# Power_Supply_HV.net
KiCad netlist of a schematic drawn in Altium Designer
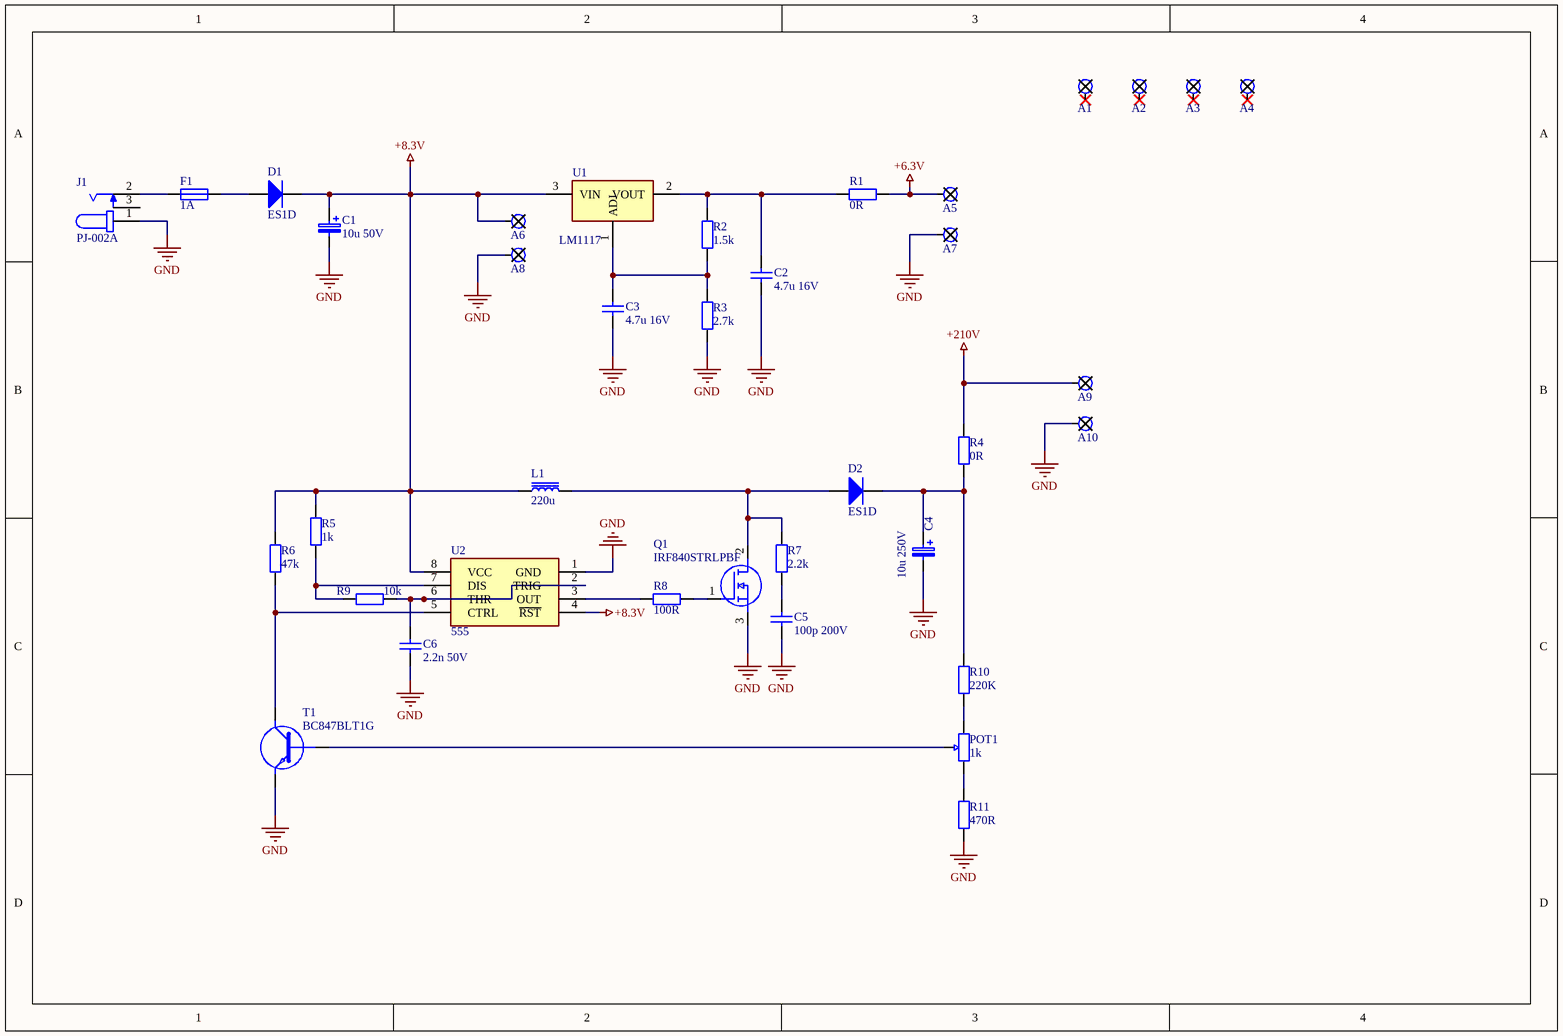
[diagram p0: Power_Supply_HV.SchDoc]

(export (version "E")
  (design (tool "Eeschema 10.0.6"))
  (components
    (comp (ref "A1")
      (value "6mm")
      (footprint "FOOTPRINTS:HOLE M6")
      (description "Mechanical M6 Hole")
      (libsource (lib "SYMBOLS") (part "Mechanical M6 Hole"))
    )
    (comp (ref "A2")
      (value "6mm")
      (footprint "FOOTPRINTS:HOLE M6")
      (description "Mechanical M6 Hole")
      (libsource (lib "SYMBOLS") (part "Mechanical M6 Hole"))
    )
    (comp (ref "A3")
      (value "6mm")
      (footprint "FOOTPRINTS:HOLE M6")
      (description "Mechanical M6 Hole")
      (libsource (lib "SYMBOLS") (part "Mechanical M6 Hole"))
    )
    (comp (ref "A4")
      (value "6mm")
      (footprint "FOOTPRINTS:HOLE M6")
      (description "Mechanical M6 Hole")
      (libsource (lib "SYMBOLS") (part "Mechanical M6 Hole"))
    )
    (comp (ref "A5")
      (value "3mm")
      (footprint "FOOTPRINTS:HOLE M3")
      (description "Mechanical M3 Hole")
      (libsource (lib "SYMBOLS") (part "Mechanical M3 Hole"))
    )
    (comp (ref "A6")
      (value "3mm")
      (footprint "FOOTPRINTS:HOLE M3")
      (description "Mechanical M3 Hole")
      (libsource (lib "SYMBOLS") (part "Mechanical M3 Hole"))
    )
    (comp (ref "A7")
      (value "3mm")
      (footprint "FOOTPRINTS:HOLE M3")
      (description "Mechanical M3 Hole")
      (libsource (lib "SYMBOLS") (part "Mechanical M3 Hole"))
    )
    (comp (ref "A8")
      (value "3mm")
      (footprint "FOOTPRINTS:HOLE M3")
      (description "Mechanical M3 Hole")
      (libsource (lib "SYMBOLS") (part "Mechanical M3 Hole"))
    )
    (comp (ref "A9")
      (value "3mm")
      (footprint "FOOTPRINTS:HOLE M3")
      (description "Mechanical M3 Hole")
      (libsource (lib "SYMBOLS") (part "Mechanical M3 Hole"))
    )
    (comp (ref "A10")
      (value "3mm")
      (footprint "FOOTPRINTS:HOLE M3")
      (description "Mechanical M3 Hole")
      (libsource (lib "SYMBOLS") (part "Mechanical M3 Hole"))
    )
    (comp (ref "C1")
      (value "10u 50V")
      (footprint "FOOTPRINTS:CAPACITOR 6.3X11MM THT")
      (description "Aluminum Electrolytic Capacitors - Radial Leaded WCAP-ATET 10uF 50V 20% Radial")
      (fields
        (field (name "MANUFACTURER") "Wurth Elektronik")
        (field (name "MANUFACTURER PART NUMBER") "860130673001")
      )
      (libsource (lib "SYMBOLS") (part "Capacitor 10u 50V 20% Aluminum 6.3x11mm THT"))
    )
    (comp (ref "C2")
      (value "4.7u 16V")
      (footprint "FOOTPRINTS:CAPACITOR 0805")
      (description "Multilayer Ceramic Capacitors MLCC - SMD/SMT 0805 16VDC 4.7uF 10% X7R")
      (fields
        (field (name "MANUFACTURER") "Taiyo Yuden")
        (field (name "MANUFACTURER PART NUMBER") "EMK212B7475KG-T")
      )
      (libsource (lib "SYMBOLS") (part "Capacitor 4.7u 16V 10% X7R 0805"))
    )
    (comp (ref "C3")
      (value "4.7u 16V")
      (footprint "FOOTPRINTS:CAPACITOR 0805")
      (description "Multilayer Ceramic Capacitors MLCC - SMD/SMT 0805 16VDC 4.7uF 10% X7R")
      (fields
        (field (name "MANUFACTURER") "Taiyo Yuden")
        (field (name "MANUFACTURER PART NUMBER") "EMK212B7475KG-T")
      )
      (libsource (lib "SYMBOLS") (part "Capacitor 4.7u 16V 10% X7R 0805"))
    )
    (comp (ref "C4")
      (value "10u 250V")
      (footprint "FOOTPRINTS:CAPACITOR 10X20MM THT")
      (description "Aluminum Electrolytic Capacitors - Radial Leaded 25V 100uF 105C 6.3x11mm")
      (fields
        (field (name "MANUFACTURER") "Producent")
        (field (name "MANUFACTURER PART NUMBER") "PJ2E100MNN1020")
      )
      (libsource (lib "SYMBOLS") (part "Capacitor 10u 250V 20% Aluminum 10x20mm THT"))
    )
    (comp (ref "C5")
      (value "100p 200V")
      (footprint "FOOTPRINTS:CAPACITOR 1206")
      (description "Multilayer Ceramic Capacitors MLCC - SMD/SMT 200V 100pF X7R 1206 10% AEC-Q200")
      (fields
        (field (name "MANUFACTURER") "KEMET")
        (field (name "MANUFACTURER PART NUMBER") "C1206C101K2RACAUTO")
      )
      (libsource (lib "SYMBOLS") (part "Capacitor 100p 200V 10% X7R 1206"))
    )
    (comp (ref "C6")
      (value "2.2n 50V")
      (footprint "FOOTPRINTS:CAPACITOR 0603")
      (description "Multilayer Ceramic Capacitors MLCC - SMD/SMT 0603 50VDC 2200pF 10% X7R AEC-Q200")
      (fields
        (field (name "MANUFACTURER") "Taiyo Yuden")
        (field (name "MANUFACTURER PART NUMBER") "UMK107B7222KAHT")
      )
      (libsource (lib "SYMBOLS") (part "Capacitor 2.2n 50V 10% X7R 0603"))
    )
    (comp (ref "D1")
      (value "ES1D")
      (footprint "FOOTPRINTS:DIODE DO-214AC")
      (description "Rectifiers 1.0a Rectifier UF Recovery")
      (fields (field (name "MANUFACTURER") "onsemi / Fairchild"))
      (libsource (lib "SYMBOLS") (part "Diode 200V 1.5W 1A Rectifier Vf 920mV ES1D"))
    )
    (comp (ref "D2")
      (value "ES1D")
      (footprint "FOOTPRINTS:DIODE DO-214AC")
      (description "Rectifiers 1.0a Rectifier UF Recovery")
      (fields (field (name "MANUFACTURER") "onsemi / Fairchild"))
      (libsource (lib "SYMBOLS") (part "Diode 200V 1.5W 1A Rectifier Vf 920mV ES1D"))
    )
    (comp (ref "F1")
      (value "1A")
      (footprint "FOOTPRINTS:FUSE 1206")
      (description "Surface Mount Fuses 1A 63V TIME DELAY")
      (fields
        (field (name "MANUFACTURER") "Bourns")
        (field (name "MANUFACTURER PART NUMBER") "SF-1206HI100M-2")
      )
      (libsource (lib "SYMBOLS") (part "Fuse 1A 1% 1/4W 1206"))
    )
    (comp (ref "J1")
      (value "PJ-002A")
      (footprint "FOOTPRINTS:Mechanical CUI_PJ-002A")
      (description "DC Power Connectors Power Jacks")
      (fields (field (name "MANUFACTURER") "https://pl.mouser.com/datasheet/2/670/pj_002a-1778764.pdf"))
      (libsource (lib "SYMBOLS") (part "Mechanical DC Power Connectors Power Jacks"))
    )
    (comp (ref "L1")
      (value "220u")
      (footprint "FOOTPRINTS:INDUCTOR CDRH127")
      (description "Power Inductors - SMD 220uH 0.95A Dual wind inductor")
      (fields
        (field (name "MANUFACTURER") "Murata Power Solutions")
        (field (name "MANUFACTURER PART NUMBER") "49221C")
      )
      (libsource (lib "SYMBOLS") (part "Inductor 220uH 0.95A Shielded 49221C"))
    )
    (comp (ref "POT1")
      (value "1k")
      (footprint "FOOTPRINTS:POTENTIOMETER TC33X")
      (description "Trimmer Resistors - SMD TRIMMER-3MM OPEN FRAME")
      (fields (field (name "MANUFACTURER") "Bourns") (field (name "MANUFACTURER PART NUMBER") "TC33X-1-102E"))
      (libsource (lib "SYMBOLS") (part "Potentiometer PCB 1k SMD TC33X-1-102E"))
    )
    (comp (ref "Q1")
      (value "IRF840STRLPBF")
      (footprint "FOOTPRINTS:TO-263-3")
      (description "MOSFET 500V N-CH HEXFET D2-PA")
      (fields (field (name "MANUFACTURER") "Vishay Semiconductors"))
      (libsource (lib "SYMBOLS") (part "Transistor N-MOSFET 500V 8A TO-263-3 IRF840STRLPBF"))
    )
    (comp (ref "R1")
      (value "0R")
      (footprint "FOOTPRINTS:RESISTOR 0603")
      (description "Thick Film Resistors - SMD 0 Ohms 100 mW 0603 5%")
      (fields
        (field (name "MANUFACTURER") "Yageo")
        (field (name "MANUFACTURER PART NUMBER") "RC0603JR-070RL")
      )
      (libsource (lib "") (part "Resistor 0R 1% 1/10W 0603_1"))
    )
    (comp (ref "R2")
      (value "1.5k")
      (footprint "FOOTPRINTS:RESISTOR 0603")
      (description "Thin Film Resistors - SMD 1/10W 1.5K ohm 1% 50ppm")
      (fields
        (field (name "MANUFACTURER") "Yageo")
        (field (name "MANUFACTURER PART NUMBER") "RT0603FRE071K5L")
      )
      (libsource (lib "SYMBOLS") (part "Resistor 1.5k 1% 1/10W 0603"))
    )
    (comp (ref "R3")
      (value "2.7k")
      (footprint "FOOTPRINTS:RESISTOR 0603")
      (description "Thin Film Resistors - SMD 1/10W 2.7K ohm 1% 50ppm")
      (fields
        (field (name "MANUFACTURER") "Yageo")
        (field (name "MANUFACTURER PART NUMBER") "RT0603FRE072K7L")
      )
      (libsource (lib "SYMBOLS") (part "Resistor 2.7k 1% 1/10W 0603"))
    )
    (comp (ref "R4")
      (value "0R")
      (footprint "FOOTPRINTS:RESISTOR 0603")
      (description "Thick Film Resistors - SMD 0 Ohms 100 mW 0603 5%")
      (fields
        (field (name "MANUFACTURER") "Yageo")
        (field (name "MANUFACTURER PART NUMBER") "RC0603JR-070RL")
      )
      (libsource (lib "SYMBOLS") (part "Resistor 0R 1% 1/10W 0603"))
    )
    (comp (ref "R5")
      (value "1k")
      (footprint "FOOTPRINTS:RESISTOR 0603")
      (description "Thin Film Resistors - SMD 1/10W 1K ohm 1% 50ppm")
      (fields
        (field (name "MANUFACTURER") "Yageo")
        (field (name "MANUFACTURER PART NUMBER") "RT0603FRE071KL")
      )
      (libsource (lib "SYMBOLS") (part "Resistor 1k 1% 1/10W 0603"))
    )
    (comp (ref "R6")
      (value "47k")
      (footprint "FOOTPRINTS:RESISTOR 0603")
      (description "Thin Film Resistors - SMD 1/10W 47K ohm 1% 50ppm")
      (fields
        (field (name "MANUFACTURER") "Yageo")
        (field (name "MANUFACTURER PART NUMBER") "RT0603FRE1347KL")
      )
      (libsource (lib "SYMBOLS") (part "Resistor 47k 1% 1/10W 0603"))
    )
    (comp (ref "R7")
      (value "2.2k")
      (footprint "FOOTPRINTS:RESISTOR 0603")
      (description "Thin Film Resistors - SMD 1/10W 2.2K ohm 1% 50ppm")
      (fields
        (field (name "MANUFACTURER") "Yageo")
        (field (name "MANUFACTURER PART NUMBER") "RT0603FRE072K2L")
      )
      (libsource (lib "SYMBOLS") (part "Resistor 2.2k 1% 1/10W 0603"))
    )
    (comp (ref "R8")
      (value "100R")
      (footprint "FOOTPRINTS:RESISTOR 0603")
      (description "Thin Film Resistors - SMD 1/10W 100R ohm 1% 50ppm")
      (fields
        (field (name "MANUFACTURER") "Yageo")
        (field (name "MANUFACTURER PART NUMBER") "RT0603FRE07100RL")
      )
      (libsource (lib "SYMBOLS") (part "Resistor 100R 1% 1/10W 0603"))
    )
    (comp (ref "R9")
      (value "10k")
      (footprint "FOOTPRINTS:RESISTOR 0603")
      (description "Thin Film Resistors - SMD 1/10W 10K ohm 1% 50ppm")
      (fields
        (field (name "MANUFACTURER") "Yageo")
        (field (name "MANUFACTURER PART NUMBER") "RT0603FRE1310KL")
      )
      (libsource (lib "SYMBOLS") (part "Resistor 10k 1% 1/10W 0603"))
    )
    (comp (ref "R10")
      (value "220K")
      (footprint "FOOTPRINTS:RESISTOR 1206")
      (description "Thin Film Resistors - SMD 1/4W 220 kohm 1% 50ppm")
      (fields
        (field (name "MANUFACTURER") "Yageo")
        (field (name "MANUFACTURER PART NUMBER") "RT1206FRE07220KL")
      )
      (libsource (lib "SYMBOLS") (part "Resistor 220k 1% 1/4W 1206"))
    )
    (comp (ref "R11")
      (value "470R")
      (footprint "FOOTPRINTS:RESISTOR 0603")
      (description "Thin Film Resistors - SMD 1/10W 470R ohm 1% 50ppm")
      (fields
        (field (name "MANUFACTURER") "Yageo")
        (field (name "MANUFACTURER PART NUMBER") "RT0603FRE07470RL")
      )
      (libsource (lib "SYMBOLS") (part "Resistor 470R 1% 1/10W 0603"))
    )
    (comp (ref "T1")
      (value "BC847BLT1G")
      (footprint "FOOTPRINTS:SOT23-3")
      (description "Bipolar Transistors - BJT 100mA 50V NPN")
      (fields (field (name "MANUFACTURER") "onsemi"))
      (libsource (lib "SYMBOLS") (part "Transistor NPN 100mA 50V BC847BLT1G"))
    )
    (comp (ref "U1")
      (value "LM1117")
      (footprint "FOOTPRINTS:TO-252")
      (description "LDO Voltage Regulators 800MA LDO LINEAR REG")
      (fields
        (field (name "MANUFACTURER PART NUMBER") "LM1117DT-ADJ")
        (field (name "MANUFACTURER") "Texas Instruments")
      )
      (libsource (lib "SYMBOLS") (part "IC LDO ADJ 800mA TO-252 LM1117DT-ADJ"))
    )
    (comp (ref "U2")
      (value "555")
      (footprint "FOOTPRINTS:SOIC-8")
      (description "Timers & Support Products Precision")
      (fields
        (field (name "MANUFACTURER") "Texas Instruments")
        (field (name "MANUFACTURER PART NUMBER") "NE555DR")
      )
      (libsource (lib "SYMBOLS") (part "IC Timer Module 555 SO-8"))
    )
  )
  (nets
    (net (code "1") (name "+6.3V") (class "Default")
      (node (ref "A5") (pin "1") (pinfunction "1_1") (pintype "passive"))
      (node (ref "R1") (pin "2") (pinfunction "2_2") (pintype "passive"))
    )
    (net (code "2") (name "+8.3V") (class "Default")
      (node (ref "A6") (pin "1") (pinfunction "1_1") (pintype "passive"))
      (node (ref "C1") (pin "1") (pinfunction "1_1") (pintype "passive"))
      (node (ref "D1") (pin "2") (pinfunction "2_2") (pintype "passive"))
      (node (ref "L1") (pin "1") (pinfunction "1_1") (pintype "passive"))
      (node (ref "R5") (pin "2") (pinfunction "2_2") (pintype "passive"))
      (node (ref "R6") (pin "2") (pinfunction "2_2") (pintype "passive"))
      (node (ref "U1") (pin "3") (pinfunction "VIN_3") (pintype "passive"))
      (node (ref "U2") (pin "4") (pinfunction "~{RST}_4") (pintype "passive"))
      (node (ref "U2") (pin "8") (pinfunction "VCC_8") (pintype "passive"))
    )
    (net (code "3") (name "+210V") (class "Default")
      (node (ref "A9") (pin "1") (pinfunction "1_1") (pintype "passive"))
      (node (ref "R4") (pin "2") (pinfunction "2_2") (pintype "passive"))
    )
    (net (code "4") (name "GND") (class "Default")
      (node (ref "A10") (pin "1") (pinfunction "1_1") (pintype "passive"))
      (node (ref "A7") (pin "1") (pinfunction "1_1") (pintype "passive"))
      (node (ref "A8") (pin "1") (pinfunction "1_1") (pintype "passive"))
      (node (ref "C1") (pin "2") (pinfunction "2_2") (pintype "passive"))
      (node (ref "C2") (pin "1") (pinfunction "1_1") (pintype "passive"))
      (node (ref "C3") (pin "1") (pinfunction "1_1") (pintype "passive"))
      (node (ref "C4") (pin "2") (pinfunction "2_2") (pintype "passive"))
      (node (ref "C5") (pin "1") (pinfunction "1_1") (pintype "passive"))
      (node (ref "C6") (pin "1") (pinfunction "1_1") (pintype "passive"))
      (node (ref "J1") (pin "1") (pinfunction "1_1") (pintype "passive"))
      (node (ref "Q1") (pin "3") (pinfunction "S_3") (pintype "passive"))
      (node (ref "R11") (pin "1") (pinfunction "1_1") (pintype "passive"))
      (node (ref "R3") (pin "1") (pinfunction "1_1") (pintype "passive"))
      (node (ref "T1") (pin "2") (pinfunction "E_2") (pintype "passive"))
      (node (ref "U2") (pin "1") (pinfunction "GND_1") (pintype "passive"))
    )
    (net (code "5") (name "Net-(C4-Pad1)") (class "Default")
      (node (ref "C4") (pin "1") (pinfunction "1_1") (pintype "passive"))
      (node (ref "D2") (pin "2") (pinfunction "2_2") (pintype "passive"))
      (node (ref "R10") (pin "2") (pinfunction "2_2") (pintype "passive"))
      (node (ref "R4") (pin "1") (pinfunction "1_1") (pintype "passive"))
    )
    (net (code "6") (name "Net-(C5-Pad2)") (class "Default")
      (node (ref "C5") (pin "2") (pinfunction "2_2") (pintype "passive"))
      (node (ref "R7") (pin "1") (pinfunction "1_1") (pintype "passive"))
    )
    (net (code "7") (name "Net-(D1-Pad1)") (class "Default")
      (node (ref "D1") (pin "1") (pinfunction "1_1") (pintype "passive"))
      (node (ref "F1") (pin "2") (pinfunction "2_2") (pintype "passive"))
    )
    (net (code "8") (name "Net-(F1-Pad1)") (class "Default")
      (node (ref "F1") (pin "1") (pinfunction "1_1") (pintype "passive"))
      (node (ref "J1") (pin "2") (pinfunction "2_2") (pintype "passive"))
    )
    (net (code "9") (name "Net-(POT1-Pad1)") (class "Default")
      (node (ref "POT1") (pin "1") (pinfunction "1_1") (pintype "passive"))
      (node (ref "R11") (pin "2") (pinfunction "2_2") (pintype "passive"))
    )
    (net (code "10") (name "Net-(POT1-Pad3)") (class "Default")
      (node (ref "POT1") (pin "3") (pinfunction "3_3") (pintype "passive"))
      (node (ref "R10") (pin "1") (pinfunction "1_1") (pintype "passive"))
    )
    (net (code "11") (name "Net-(Q1-D)") (class "Default")
      (node (ref "D2") (pin "1") (pinfunction "1_1") (pintype "passive"))
      (node (ref "L1") (pin "2") (pinfunction "2_2") (pintype "passive"))
      (node (ref "Q1") (pin "2") (pinfunction "D_2") (pintype "passive"))
      (node (ref "R7") (pin "2") (pinfunction "2_2") (pintype "passive"))
    )
    (net (code "12") (name "Net-(Q1-G)") (class "Default")
      (node (ref "Q1") (pin "1") (pinfunction "G_1") (pintype "passive"))
      (node (ref "R8") (pin "2") (pinfunction "2_2") (pintype "passive"))
    )
    (net (code "13") (name "Net-(T1-B)") (class "Default")
      (node (ref "POT1") (pin "2") (pinfunction "2_2") (pintype "passive"))
      (node (ref "T1") (pin "1") (pinfunction "B_1") (pintype "passive"))
    )
    (net (code "14") (name "Net-(T1-C)") (class "Default")
      (node (ref "R6") (pin "1") (pinfunction "1_1") (pintype "passive"))
      (node (ref "T1") (pin "3") (pinfunction "C_3") (pintype "passive"))
      (node (ref "U2") (pin "5") (pinfunction "CTRL_5") (pintype "passive"))
    )
    (net (code "15") (name "Net-(U1-ADJ)") (class "Default")
      (node (ref "C3") (pin "2") (pinfunction "2_2") (pintype "passive"))
      (node (ref "R2") (pin "1") (pinfunction "1_1") (pintype "passive"))
      (node (ref "R3") (pin "2") (pinfunction "2_2") (pintype "passive"))
      (node (ref "U1") (pin "1") (pinfunction "ADJ_1") (pintype "passive"))
    )
    (net (code "16") (name "Net-(U1-VOUT)") (class "Default")
      (node (ref "C2") (pin "2") (pinfunction "2_2") (pintype "passive"))
      (node (ref "R1") (pin "1") (pinfunction "1_1") (pintype "passive"))
      (node (ref "R2") (pin "2") (pinfunction "2_2") (pintype "passive"))
      (node (ref "U1") (pin "2") (pinfunction "VOUT_2") (pintype "passive"))
    )
    (net (code "17") (name "Net-(U2-DIS)") (class "Default")
      (node (ref "R5") (pin "1") (pinfunction "1_1") (pintype "passive"))
      (node (ref "R9") (pin "1") (pinfunction "1_1") (pintype "passive"))
      (node (ref "U2") (pin "7") (pinfunction "DIS_7") (pintype "passive"))
    )
    (net (code "18") (name "Net-(U2-OUT)") (class "Default")
      (node (ref "R8") (pin "1") (pinfunction "1_1") (pintype "passive"))
      (node (ref "U2") (pin "3") (pinfunction "OUT_3") (pintype "passive"))
    )
    (net (code "19") (name "Net-(U2-THR)") (class "Default")
      (node (ref "C6") (pin "2") (pinfunction "2_2") (pintype "passive"))
      (node (ref "R9") (pin "2") (pinfunction "2_2") (pintype "passive"))
      (node (ref "U2") (pin "2") (pinfunction "TRIG_2") (pintype "passive"))
      (node (ref "U2") (pin "6") (pinfunction "THR_6") (pintype "passive"))
    )
    (net (code "20") (name "unconnected-(A1-Pad1)") (class "Default")
      (node (ref "A1") (pin "1") (pinfunction "1_1") (pintype "passive+no_connect"))
    )
    (net (code "21") (name "unconnected-(A2-Pad1)") (class "Default")
      (node (ref "A2") (pin "1") (pinfunction "1_1") (pintype "passive+no_connect"))
    )
    (net (code "22") (name "unconnected-(A3-Pad1)") (class "Default")
      (node (ref "A3") (pin "1") (pinfunction "1_1") (pintype "passive+no_connect"))
    )
    (net (code "23") (name "unconnected-(A4-Pad1)") (class "Default")
      (node (ref "A4") (pin "1") (pinfunction "1_1") (pintype "passive+no_connect"))
    )
    (net (code "24") (name "unconnected-(J1-Pad3)") (class "Default")
      (node (ref "J1") (pin "3") (pinfunction "3_3") (pintype "passive"))
    )
  )
)
